# FREZZbigV02.net
KiCad netlist of a schematic drawn in EAGLE
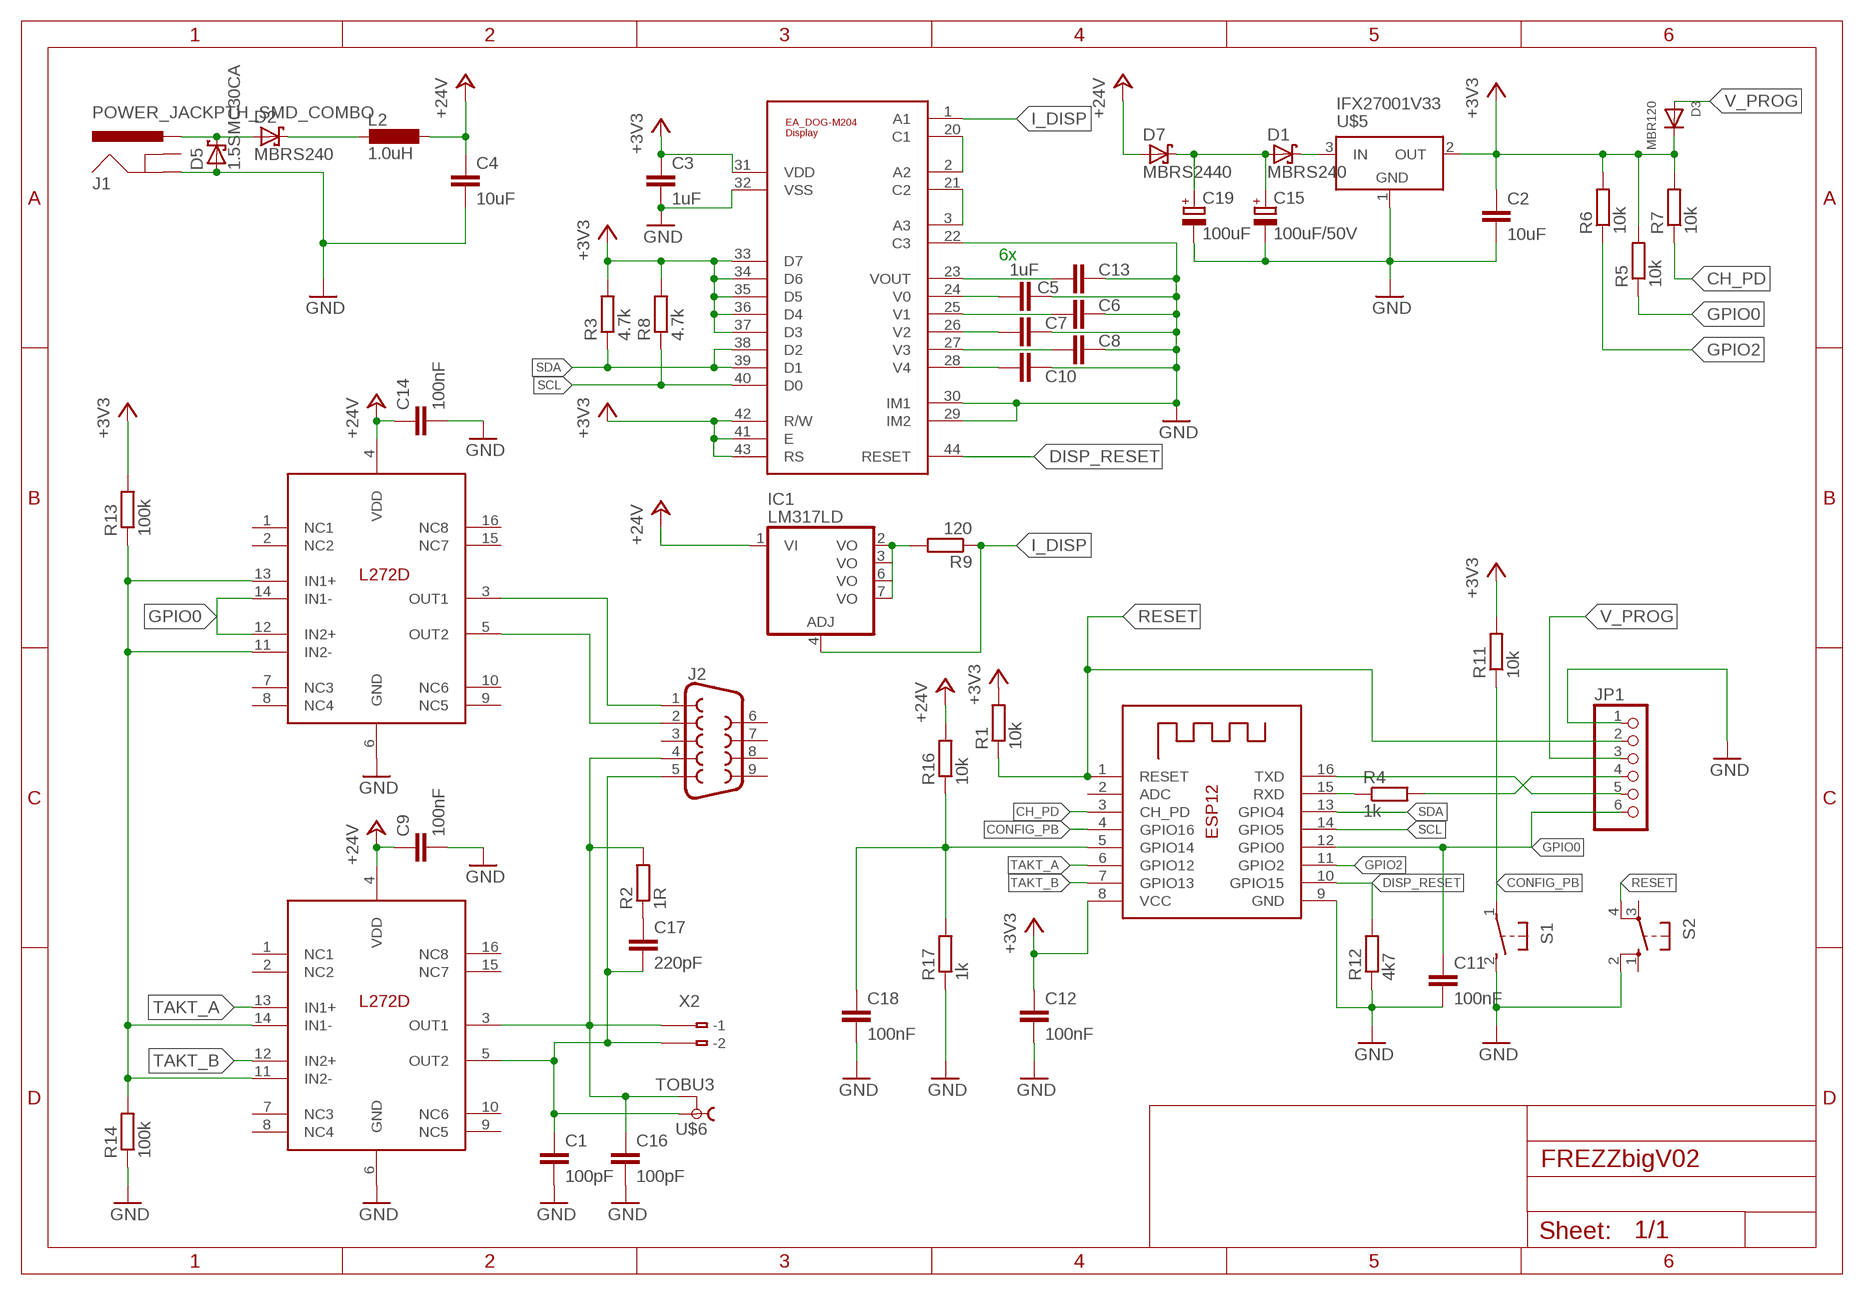
[diagram p0: schematic, sheet 1]

(export (version "E")
  (design (tool "Eeschema 10.0.6"))
  (components
    (comp (ref "C1")
      (value "100pF")
      (footprint "eagle-import:C0603K")
      (libsource (lib "eagle-import") (part "C-EUC0603K"))
    )
    (comp (ref "C2")
      (value "10uF")
      (footprint "eagle-import:C0603K")
      (libsource (lib "eagle-import") (part "C-EUC0603K"))
    )
    (comp (ref "C3")
      (value "1uF")
      (footprint "eagle-import:C0603K")
      (libsource (lib "eagle-import") (part "C-EUC0603K"))
    )
    (comp (ref "C4")
      (value "10uF")
      (footprint "eagle-import:C1210K")
      (libsource (lib "eagle-import") (part "C-EUC1210K"))
    )
    (comp (ref "C5")
      (value "1uF")
      (footprint "eagle-import:C0603K")
      (libsource (lib "eagle-import") (part "C-EUC0603K"))
    )
    (comp (ref "C6")
      (value "1uF")
      (footprint "eagle-import:C0603K")
      (libsource (lib "eagle-import") (part "C-EUC0603K"))
    )
    (comp (ref "C7")
      (value "1uF")
      (footprint "eagle-import:C0603K")
      (libsource (lib "eagle-import") (part "C-EUC0603K"))
    )
    (comp (ref "C8")
      (value "1uF")
      (footprint "eagle-import:C0603K")
      (libsource (lib "eagle-import") (part "C-EUC0603K"))
    )
    (comp (ref "C9")
      (value "100nF")
      (footprint "eagle-import:C0603K")
      (libsource (lib "eagle-import") (part "C-EUC0603K"))
    )
    (comp (ref "C10")
      (value "1uF")
      (footprint "eagle-import:C0603K")
      (libsource (lib "eagle-import") (part "C-EUC0603K"))
    )
    (comp (ref "C11")
      (value "100nF")
      (footprint "eagle-import:C0603K")
      (libsource (lib "eagle-import") (part "C-EUC0603K"))
    )
    (comp (ref "C12")
      (value "100nF")
      (footprint "eagle-import:C0603K")
      (libsource (lib "eagle-import") (part "C-EUC0603K"))
    )
    (comp (ref "C13")
      (value "1uF")
      (footprint "eagle-import:C0603K")
      (libsource (lib "eagle-import") (part "C-EUC0603K"))
    )
    (comp (ref "C14")
      (value "100nF")
      (footprint "eagle-import:C0603K")
      (libsource (lib "eagle-import") (part "C-EUC0603K"))
    )
    (comp (ref "C15")
      (value "100uF/50V")
      (footprint "eagle-import:PANASONIC_F")
      (libsource (lib "eagle-import") (part "CPOL-EUF"))
    )
    (comp (ref "C16")
      (value "100pF")
      (footprint "eagle-import:C0603K")
      (libsource (lib "eagle-import") (part "C-EUC0603K"))
    )
    (comp (ref "C17")
      (value "220pF")
      (footprint "eagle-import:C0603K")
      (libsource (lib "eagle-import") (part "C-EUC0603K"))
    )
    (comp (ref "C18")
      (value "100nF")
      (footprint "eagle-import:C0603K")
      (libsource (lib "eagle-import") (part "C-EUC0603K"))
    )
    (comp (ref "C19")
      (value "100uF")
      (footprint "eagle-import:E7,5-18")
      (libsource (lib "eagle-import") (part "CPOL-EUE7.5-18"))
    )
    (comp (ref "D1")
      (value "MBRS240")
      (footprint "eagle-import:SMB")
      (libsource (lib "eagle-import") (part "SCHOTTKY-DIODESMD"))
    )
    (comp (ref "D2")
      (value "MBRS240")
      (footprint "eagle-import:SMB")
      (libsource (lib "eagle-import") (part "SCHOTTKY-DIODESMD"))
    )
    (comp (ref "D3")
      (value "MBR120")
      (footprint "eagle-import:SOD-123")
      (libsource (lib "eagle-import") (part "DIODESOD-123"))
    )
    (comp (ref "D5")
      (value "1.5SMC30CA")
      (footprint "eagle-import:SMC")
      (libsource (lib "eagle-import") (part "SCHOTTKY-DIODESMC"))
    )
    (comp (ref "D7")
      (value "MBRS2440")
      (footprint "eagle-import:SMB")
      (libsource (lib "eagle-import") (part "SCHOTTKY-DIODESMD"))
    )
    (comp (ref "IC1")
      (value "LM317LD")
      (footprint "eagle-import:SO08")
      (libsource (lib "eagle-import") (part "LM317LD"))
    )
    (comp (ref "J1")
      (value "POWER_JACKPTH_SMD_COMBO")
      (footprint "eagle-import:POWER_JACK_COMBO")
      (libsource (lib "eagle-import") (part "POWER_JACKPTH_SMD_COMBO"))
    )
    (comp (ref "J2")
      (value "DB9FEMALE")
      (footprint "eagle-import:DB9")
      (libsource (lib "eagle-import") (part "DB9FEMALE"))
    )
    (comp (ref "JP1")
      (value "PINHD-1X6")
      (footprint "eagle-import:1X06")
      (libsource (lib "eagle-import") (part "PINHD-1X6"))
    )
    (comp (ref "L2")
      (value "1.0uH")
      (footprint "eagle-import:L3230M")
      (libsource (lib "eagle-import") (part "L-EUL3230M"))
    )
    (comp (ref "R1")
      (value "10k")
      (footprint "eagle-import:M1206")
      (libsource (lib "eagle-import") (part "R-EU_M1206"))
    )
    (comp (ref "R2")
      (value "1R")
      (footprint "eagle-import:M1206")
      (libsource (lib "eagle-import") (part "R-EU_M1206"))
    )
    (comp (ref "R3")
      (value "4.7k")
      (footprint "eagle-import:M1206")
      (libsource (lib "eagle-import") (part "R-EU_M1206"))
    )
    (comp (ref "R4")
      (value "1k")
      (footprint "eagle-import:M1206")
      (libsource (lib "eagle-import") (part "R-EU_M1206"))
    )
    (comp (ref "R5")
      (value "10k")
      (footprint "eagle-import:M1206")
      (libsource (lib "eagle-import") (part "R-EU_M1206"))
    )
    (comp (ref "R6")
      (value "10k")
      (footprint "eagle-import:M1206")
      (libsource (lib "eagle-import") (part "R-EU_M1206"))
    )
    (comp (ref "R7")
      (value "10k")
      (footprint "eagle-import:M1206")
      (libsource (lib "eagle-import") (part "R-EU_M1206"))
    )
    (comp (ref "R8")
      (value "4.7k")
      (footprint "eagle-import:M1206")
      (libsource (lib "eagle-import") (part "R-EU_M1206"))
    )
    (comp (ref "R9")
      (value "120")
      (footprint "eagle-import:M1206")
      (libsource (lib "eagle-import") (part "R-EU_M1206"))
    )
    (comp (ref "R11")
      (value "10k")
      (footprint "eagle-import:M1206")
      (libsource (lib "eagle-import") (part "R-EU_M1206"))
    )
    (comp (ref "R12")
      (value "4k7")
      (footprint "eagle-import:M1206")
      (libsource (lib "eagle-import") (part "R-EU_M1206"))
    )
    (comp (ref "R13")
      (value "100k")
      (footprint "eagle-import:M1206")
      (libsource (lib "eagle-import") (part "R-EU_M1206"))
    )
    (comp (ref "R14")
      (value "100k")
      (footprint "eagle-import:M1206")
      (libsource (lib "eagle-import") (part "R-EU_M1206"))
    )
    (comp (ref "R16")
      (value "10k")
      (footprint "eagle-import:M1206")
      (libsource (lib "eagle-import") (part "R-EU_M1206"))
    )
    (comp (ref "R17")
      (value "1k")
      (footprint "eagle-import:M1206")
      (libsource (lib "eagle-import") (part "R-EU_M1206"))
    )
    (comp (ref "S1")
      (value "31-XX")
      (footprint "eagle-import:B3F-31XX")
      (fields (field (name "MPN") "B3F-3100"))
      (libsource (lib "eagle-import") (part "31-XX"))
    )
    (comp (ref "S2")
      (value "10-XX")
      (footprint "eagle-import:B3F-10XX")
      (fields (field (name "MPN") "B3F-1000"))
      (libsource (lib "eagle-import") (part "10-XX"))
    )
    (comp (ref "U$1")
      (value "EA_DOG-M204-DISPLAY")
      (footprint "eagle-import:E_DOG-M204_DISPLAY")
      (libsource (lib "eagle-import") (part "EA_DOG-M204-DISPLAY"))
    )
    (comp (ref "U$2")
      (value "L272D")
      (footprint "eagle-import:SO16")
      (libsource (lib "eagle-import") (part "L272D"))
    )
    (comp (ref "U$3")
      (value "L272D")
      (footprint "eagle-import:SO16")
      (libsource (lib "eagle-import") (part "L272D"))
    )
    (comp (ref "U$5")
      (value "IFX27001V33")
      (footprint "eagle-import:TO252")
      (libsource (lib "eagle-import") (part "IFX27001"))
    )
    (comp (ref "U$6")
      (value "TOBU3")
      (footprint "eagle-import:TOBU3-REICHELT")
      (libsource (lib "eagle-import") (part "TOBU3-REICHELT"))
    )
    (comp (ref "X1")
      (value "ESP-12")
      (footprint "eagle-import:ESP-12")
      (libsource (lib "eagle-import") (part "ESP-12"))
    )
    (comp (ref "X2")
      (value "233-102")
      (footprint "eagle-import:233-102")
      (libsource (lib "eagle-import") (part "233-102"))
    )
  )
  (nets
    (net (code "1") (name "+3V3") (class "Default")
      (node (ref "C12") (pin "1") (pinfunction "1_1") (pintype "passive"))
      (node (ref "C2") (pin "1") (pinfunction "1_1") (pintype "passive"))
      (node (ref "C3") (pin "1") (pinfunction "1_1") (pintype "passive"))
      (node (ref "D3") (pin "C") (pinfunction "C_C") (pintype "passive"))
      (node (ref "R1") (pin "2") (pinfunction "2_2") (pintype "passive"))
      (node (ref "R11") (pin "2") (pinfunction "2_2") (pintype "passive"))
      (node (ref "R13") (pin "2") (pinfunction "2_2") (pintype "passive"))
      (node (ref "R3") (pin "2") (pinfunction "2_2") (pintype "passive"))
      (node (ref "R5") (pin "2") (pinfunction "2_2") (pintype "passive"))
      (node (ref "R6") (pin "2") (pinfunction "2_2") (pintype "passive"))
      (node (ref "R7") (pin "2") (pinfunction "2_2") (pintype "passive"))
      (node (ref "R8") (pin "2") (pinfunction "2_2") (pintype "passive"))
      (node (ref "U$1") (pin "31") (pinfunction "VDD_31") (pintype "power_in"))
      (node (ref "U$1") (pin "33") (pinfunction "D7_33") (pintype "bidirectional"))
      (node (ref "U$1") (pin "34") (pinfunction "D6_34") (pintype "bidirectional"))
      (node (ref "U$1") (pin "35") (pinfunction "D5_35") (pintype "bidirectional"))
      (node (ref "U$1") (pin "36") (pinfunction "D4_36") (pintype "bidirectional"))
      (node (ref "U$1") (pin "37") (pinfunction "D3_37") (pintype "bidirectional"))
      (node (ref "U$1") (pin "41") (pinfunction "E_41") (pintype "bidirectional"))
      (node (ref "U$1") (pin "42") (pinfunction "R/W_42") (pintype "bidirectional"))
      (node (ref "U$1") (pin "43") (pinfunction "RS_43") (pintype "bidirectional"))
      (node (ref "U$5") (pin "2") (pinfunction "OUT_2") (pintype "output"))
      (node (ref "X1") (pin "8") (pinfunction "VCC_8") (pintype "power_in"))
    )
    (net (code "2") (name "+24V") (class "Default")
      (node (ref "C14") (pin "1") (pinfunction "1_1") (pintype "passive"))
      (node (ref "C4") (pin "1") (pinfunction "1_1") (pintype "passive"))
      (node (ref "C9") (pin "1") (pinfunction "1_1") (pintype "passive"))
      (node (ref "D7") (pin "A") (pinfunction "A_A") (pintype "passive"))
      (node (ref "IC1") (pin "1") (pinfunction "VI_1") (pintype "input"))
      (node (ref "L2") (pin "1") (pinfunction "1_1") (pintype "passive"))
      (node (ref "R16") (pin "2") (pinfunction "2_2") (pintype "passive"))
      (node (ref "U$2") (pin "4") (pinfunction "VDD_4") (pintype "power_in"))
      (node (ref "U$3") (pin "4") (pinfunction "VDD_4") (pintype "power_in"))
    )
    (net (code "3") (name "CH_PD") (class "Default")
      (node (ref "R7") (pin "1") (pinfunction "1_1") (pintype "passive"))
      (node (ref "X1") (pin "3") (pinfunction "CH_PD_3") (pintype "input"))
    )
    (net (code "4") (name "CONFIG_PB") (class "Default")
      (node (ref "R11") (pin "1") (pinfunction "1_1") (pintype "passive"))
      (node (ref "S1") (pin "1") (pinfunction "P_1") (pintype "passive"))
      (node (ref "X1") (pin "4") (pinfunction "GPIO16_4") (pintype "bidirectional"))
    )
    (net (code "5") (name "DISP_RESET") (class "Default")
      (node (ref "R12") (pin "2") (pinfunction "2_2") (pintype "passive"))
      (node (ref "U$1") (pin "44") (pinfunction "RESET_44") (pintype "bidirectional"))
      (node (ref "X1") (pin "10") (pinfunction "GPIO15_10") (pintype "bidirectional"))
    )
    (net (code "6") (name "GND") (class "Default")
      (node (ref "C1") (pin "2") (pinfunction "2_2") (pintype "passive"))
      (node (ref "C10") (pin "1") (pinfunction "1_1") (pintype "passive"))
      (node (ref "C11") (pin "2") (pinfunction "2_2") (pintype "passive"))
      (node (ref "C12") (pin "2") (pinfunction "2_2") (pintype "passive"))
      (node (ref "C13") (pin "1") (pinfunction "1_1") (pintype "passive"))
      (node (ref "C14") (pin "2") (pinfunction "2_2") (pintype "passive"))
      (node (ref "C15") (pin "-") (pinfunction "-_-") (pintype "passive"))
      (node (ref "C16") (pin "2") (pinfunction "2_2") (pintype "passive"))
      (node (ref "C18") (pin "2") (pinfunction "2_2") (pintype "passive"))
      (node (ref "C19") (pin "-") (pinfunction "-_-") (pintype "passive"))
      (node (ref "C2") (pin "2") (pinfunction "2_2") (pintype "passive"))
      (node (ref "C3") (pin "2") (pinfunction "2_2") (pintype "passive"))
      (node (ref "C4") (pin "2") (pinfunction "2_2") (pintype "passive"))
      (node (ref "C5") (pin "1") (pinfunction "1_1") (pintype "passive"))
      (node (ref "C6") (pin "1") (pinfunction "1_1") (pintype "passive"))
      (node (ref "C7") (pin "1") (pinfunction "1_1") (pintype "passive"))
      (node (ref "C8") (pin "1") (pinfunction "1_1") (pintype "passive"))
      (node (ref "C9") (pin "2") (pinfunction "2_2") (pintype "passive"))
      (node (ref "D5") (pin "A") (pinfunction "A_A") (pintype "passive"))
      (node (ref "J1") (pin "GND@1") (pinfunction "GND_GND@1") (pintype "bidirectional"))
      (node (ref "JP1") (pin "1") (pinfunction "1_1") (pintype "passive"))
      (node (ref "R12") (pin "1") (pinfunction "1_1") (pintype "passive"))
      (node (ref "R14") (pin "1") (pinfunction "1_1") (pintype "passive"))
      (node (ref "R17") (pin "1") (pinfunction "1_1") (pintype "passive"))
      (node (ref "S1") (pin "2") (pinfunction "S_2") (pintype "passive"))
      (node (ref "S2") (pin "2") (pinfunction "S1_2") (pintype "passive"))
      (node (ref "U$1") (pin "22") (pinfunction "C3_22") (pintype "bidirectional"))
      (node (ref "U$1") (pin "29") (pinfunction "IM2_29") (pintype "bidirectional"))
      (node (ref "U$1") (pin "30") (pinfunction "IM1_30") (pintype "bidirectional"))
      (node (ref "U$1") (pin "32") (pinfunction "VSS_32") (pintype "power_in"))
      (node (ref "U$2") (pin "6") (pinfunction "GND_6") (pintype "power_in"))
      (node (ref "U$3") (pin "6") (pinfunction "GND_6") (pintype "power_in"))
      (node (ref "U$5") (pin "1") (pinfunction "GND_1") (pintype "power_in"))
      (node (ref "X1") (pin "9") (pinfunction "GND_9") (pintype "power_in"))
    )
    (net (code "7") (name "GPIO0") (class "Default")
      (node (ref "C11") (pin "1") (pinfunction "1_1") (pintype "passive"))
      (node (ref "JP1") (pin "6") (pinfunction "6_6") (pintype "passive"))
      (node (ref "R5") (pin "1") (pinfunction "1_1") (pintype "passive"))
      (node (ref "U$3") (pin "12") (pinfunction "IN2+_12") (pintype "bidirectional"))
      (node (ref "U$3") (pin "14") (pinfunction "IN1-_14") (pintype "bidirectional"))
      (node (ref "X1") (pin "12") (pinfunction "GPIO0_12") (pintype "bidirectional"))
    )
    (net (code "8") (name "GPIO2") (class "Default")
      (node (ref "R6") (pin "1") (pinfunction "1_1") (pintype "passive"))
      (node (ref "X1") (pin "11") (pinfunction "GPIO2_11") (pintype "bidirectional"))
    )
    (net (code "9") (name "I_DISP") (class "Default")
      (node (ref "IC1") (pin "4") (pinfunction "ADJ_4") (pintype "input"))
      (node (ref "R9") (pin "1") (pinfunction "1_1") (pintype "passive"))
      (node (ref "U$1") (pin "1") (pinfunction "A1_1") (pintype "bidirectional"))
    )
    (net (code "10") (name "Net-(C15-Pad+)") (class "Default")
      (node (ref "C15") (pin "+") (pinfunction "+_+") (pintype "passive"))
      (node (ref "C19") (pin "+") (pinfunction "+_+") (pintype "passive"))
      (node (ref "D1") (pin "A") (pinfunction "A_A") (pintype "passive"))
      (node (ref "D7") (pin "C") (pinfunction "C_C") (pintype "passive"))
    )
    (net (code "11") (name "Net-(C17-Pad1)") (class "Default")
      (node (ref "C17") (pin "1") (pinfunction "1_1") (pintype "passive"))
      (node (ref "R2") (pin "1") (pinfunction "1_1") (pintype "passive"))
    )
    (net (code "12") (name "Net-(D2-PadC)") (class "Default")
      (node (ref "D2") (pin "C") (pinfunction "C_C") (pintype "passive"))
      (node (ref "L2") (pin "2") (pinfunction "2_2") (pintype "passive"))
    )
    (net (code "13") (name "Net-(IC1-VO-Pad2)") (class "Default")
      (node (ref "IC1") (pin "2") (pinfunction "VO_2") (pintype "passive"))
      (node (ref "IC1") (pin "3") (pinfunction "VO_3") (pintype "passive"))
      (node (ref "IC1") (pin "6") (pinfunction "VO_6") (pintype "passive"))
      (node (ref "IC1") (pin "7") (pinfunction "VO_7") (pintype "passive"))
      (node (ref "R9") (pin "2") (pinfunction "2_2") (pintype "passive"))
    )
    (net (code "14") (name "Net-(J1-PWR)") (class "Default")
      (node (ref "D2") (pin "A") (pinfunction "A_A") (pintype "passive"))
      (node (ref "D5") (pin "C") (pinfunction "C_C") (pintype "passive"))
      (node (ref "J1") (pin "POWER") (pinfunction "PWR_POWER") (pintype "bidirectional"))
    )
    (net (code "15") (name "Net-(JP1-Pad4)") (class "Default")
      (node (ref "JP1") (pin "4") (pinfunction "4_4") (pintype "passive"))
      (node (ref "R4") (pin "2") (pinfunction "2_2") (pintype "passive"))
    )
    (net (code "16") (name "Net-(U$1-A2)") (class "Default")
      (node (ref "U$1") (pin "2") (pinfunction "A2_2") (pintype "bidirectional"))
      (node (ref "U$1") (pin "20") (pinfunction "C1_20") (pintype "bidirectional"))
    )
    (net (code "17") (name "Net-(U$1-A3)") (class "Default")
      (node (ref "U$1") (pin "21") (pinfunction "C2_21") (pintype "bidirectional"))
      (node (ref "U$1") (pin "3") (pinfunction "A3_3") (pintype "bidirectional"))
    )
    (net (code "18") (name "Net-(U$1-V0)") (class "Default")
      (node (ref "C5") (pin "2") (pinfunction "2_2") (pintype "passive"))
      (node (ref "U$1") (pin "24") (pinfunction "V0_24") (pintype "bidirectional"))
    )
    (net (code "19") (name "Net-(U$1-V1)") (class "Default")
      (node (ref "C6") (pin "2") (pinfunction "2_2") (pintype "passive"))
      (node (ref "U$1") (pin "25") (pinfunction "V1_25") (pintype "bidirectional"))
    )
    (net (code "20") (name "Net-(U$1-V2)") (class "Default")
      (node (ref "C7") (pin "2") (pinfunction "2_2") (pintype "passive"))
      (node (ref "U$1") (pin "26") (pinfunction "V2_26") (pintype "bidirectional"))
    )
    (net (code "21") (name "Net-(U$1-V3)") (class "Default")
      (node (ref "C8") (pin "2") (pinfunction "2_2") (pintype "passive"))
      (node (ref "U$1") (pin "27") (pinfunction "V3_27") (pintype "bidirectional"))
    )
    (net (code "22") (name "Net-(U$1-V4)") (class "Default")
      (node (ref "C10") (pin "2") (pinfunction "2_2") (pintype "passive"))
      (node (ref "U$1") (pin "28") (pinfunction "V4_28") (pintype "bidirectional"))
    )
    (net (code "23") (name "Net-(U$1-VOUT)") (class "Default")
      (node (ref "C13") (pin "2") (pinfunction "2_2") (pintype "passive"))
      (node (ref "U$1") (pin "23") (pinfunction "VOUT_23") (pintype "bidirectional"))
    )
    (net (code "24") (name "Net-(U$2-IN1-)") (class "Default")
      (node (ref "R13") (pin "1") (pinfunction "1_1") (pintype "passive"))
      (node (ref "R14") (pin "2") (pinfunction "2_2") (pintype "passive"))
      (node (ref "U$2") (pin "11") (pinfunction "IN2-_11") (pintype "bidirectional"))
      (node (ref "U$2") (pin "14") (pinfunction "IN1-_14") (pintype "bidirectional"))
      (node (ref "U$3") (pin "11") (pinfunction "IN2-_11") (pintype "bidirectional"))
      (node (ref "U$3") (pin "13") (pinfunction "IN1+_13") (pintype "input"))
    )
    (net (code "25") (name "Net-(U$2-OUT1)") (class "Default")
      (node (ref "C16") (pin "1") (pinfunction "1_1") (pintype "passive"))
      (node (ref "J2") (pin "4") (pinfunction "4_4") (pintype "passive"))
      (node (ref "R2") (pin "2") (pinfunction "2_2") (pintype "passive"))
      (node (ref "U$2") (pin "3") (pinfunction "OUT1_3") (pintype "output"))
      (node (ref "U$6") (pin "2") (pinfunction "2_2") (pintype "passive"))
      (node (ref "U$6") (pin "2@1") (pinfunction "2_2@1") (pintype "passive"))
      (node (ref "U$6") (pin "2@2") (pinfunction "2_2@2") (pintype "passive"))
      (node (ref "X2") (pin "B1") (pinfunction "B-1_B1") (pintype "passive"))
    )
    (net (code "26") (name "Net-(U$2-OUT2)") (class "Default")
      (node (ref "C1") (pin "1") (pinfunction "1_1") (pintype "passive"))
      (node (ref "C17") (pin "2") (pinfunction "2_2") (pintype "passive"))
      (node (ref "J2") (pin "5") (pinfunction "5_5") (pintype "passive"))
      (node (ref "U$2") (pin "5") (pinfunction "OUT2_5") (pintype "output"))
      (node (ref "U$6") (pin "1") (pinfunction "1_1") (pintype "passive"))
      (node (ref "X2") (pin "B2") (pinfunction "B-2_B2") (pintype "passive"))
    )
    (net (code "27") (name "Net-(U$3-OUT1)") (class "Default")
      (node (ref "J2") (pin "1") (pinfunction "1_1") (pintype "passive"))
      (node (ref "U$3") (pin "3") (pinfunction "OUT1_3") (pintype "output"))
    )
    (net (code "28") (name "Net-(U$3-OUT2)") (class "Default")
      (node (ref "J2") (pin "2") (pinfunction "2_2") (pintype "passive"))
      (node (ref "U$3") (pin "5") (pinfunction "OUT2_5") (pintype "output"))
    )
    (net (code "29") (name "Net-(U$5-IN)") (class "Default")
      (node (ref "D1") (pin "C") (pinfunction "C_C") (pintype "passive"))
      (node (ref "U$5") (pin "3") (pinfunction "IN_3") (pintype "input"))
    )
    (net (code "30") (name "Net-(X1-GPIO14)") (class "Default")
      (node (ref "C18") (pin "1") (pinfunction "1_1") (pintype "passive"))
      (node (ref "R16") (pin "1") (pinfunction "1_1") (pintype "passive"))
      (node (ref "R17") (pin "2") (pinfunction "2_2") (pintype "passive"))
      (node (ref "X1") (pin "5") (pinfunction "GPIO14_5") (pintype "bidirectional"))
    )
    (net (code "31") (name "Net-(X1-RXD)") (class "Default")
      (node (ref "R4") (pin "1") (pinfunction "1_1") (pintype "passive"))
      (node (ref "X1") (pin "15") (pinfunction "RXD_15") (pintype "input"))
    )
    (net (code "32") (name "Net-(X1-TXD)") (class "Default")
      (node (ref "JP1") (pin "5") (pinfunction "5_5") (pintype "passive"))
      (node (ref "X1") (pin "16") (pinfunction "TXD_16") (pintype "output"))
    )
    (net (code "33") (name "RESET") (class "Default")
      (node (ref "JP1") (pin "2") (pinfunction "2_2") (pintype "passive"))
      (node (ref "R1") (pin "1") (pinfunction "1_1") (pintype "passive"))
      (node (ref "S2") (pin "4") (pinfunction "P1_4") (pintype "passive"))
      (node (ref "X1") (pin "1") (pinfunction "RESET_1") (pintype "input"))
    )
    (net (code "34") (name "SCL") (class "Default")
      (node (ref "R8") (pin "1") (pinfunction "1_1") (pintype "passive"))
      (node (ref "U$1") (pin "40") (pinfunction "D0_40") (pintype "bidirectional"))
      (node (ref "X1") (pin "14") (pinfunction "GPIO5_14") (pintype "bidirectional"))
    )
    (net (code "35") (name "SDA") (class "Default")
      (node (ref "R3") (pin "1") (pinfunction "1_1") (pintype "passive"))
      (node (ref "U$1") (pin "38") (pinfunction "D2_38") (pintype "bidirectional"))
      (node (ref "U$1") (pin "39") (pinfunction "D1_39") (pintype "bidirectional"))
      (node (ref "X1") (pin "13") (pinfunction "GPIO4_13") (pintype "bidirectional"))
    )
    (net (code "36") (name "TAKT_A") (class "Default")
      (node (ref "U$2") (pin "13") (pinfunction "IN1+_13") (pintype "input"))
      (node (ref "X1") (pin "6") (pinfunction "GPIO12_6") (pintype "bidirectional"))
    )
    (net (code "37") (name "TAKT_B") (class "Default")
      (node (ref "U$2") (pin "12") (pinfunction "IN2+_12") (pintype "bidirectional"))
      (node (ref "X1") (pin "7") (pinfunction "GPIO13_7") (pintype "bidirectional"))
    )
    (net (code "38") (name "V_PROG") (class "Default")
      (node (ref "D3") (pin "A") (pinfunction "A_A") (pintype "passive"))
      (node (ref "JP1") (pin "3") (pinfunction "3_3") (pintype "passive"))
    )
    (net (code "39") (name "unconnected-(J1-GNDBREAK-PadGND)") (class "Default")
      (node (ref "J1") (pin "GND") (pinfunction "GNDBREAK_GND") (pintype "bidirectional"))
    )
    (net (code "40") (name "unconnected-(J2-Pad3)") (class "Default")
      (node (ref "J2") (pin "3") (pinfunction "3_3") (pintype "passive"))
    )
    (net (code "41") (name "unconnected-(J2-Pad6)") (class "Default")
      (node (ref "J2") (pin "6") (pinfunction "6_6") (pintype "passive"))
    )
    (net (code "42") (name "unconnected-(J2-Pad7)") (class "Default")
      (node (ref "J2") (pin "7") (pinfunction "7_7") (pintype "passive"))
    )
    (net (code "43") (name "unconnected-(J2-Pad8)") (class "Default")
      (node (ref "J2") (pin "8") (pinfunction "8_8") (pintype "passive"))
    )
    (net (code "44") (name "unconnected-(J2-Pad9)") (class "Default")
      (node (ref "J2") (pin "9") (pinfunction "9_9") (pintype "passive"))
    )
    (net (code "45") (name "unconnected-(S2-P-Pad3)") (class "Default")
      (node (ref "S2") (pin "3") (pinfunction "P_3") (pintype "passive"))
    )
    (net (code "46") (name "unconnected-(S2-S-Pad1)") (class "Default")
      (node (ref "S2") (pin "1") (pinfunction "S_1") (pintype "passive"))
    )
    (net (code "47") (name "unconnected-(U$2-NC1-Pad1)") (class "Default")
      (node (ref "U$2") (pin "1") (pinfunction "NC1_1") (pintype "no_connect"))
    )
    (net (code "48") (name "unconnected-(U$2-NC2-Pad2)") (class "Default")
      (node (ref "U$2") (pin "2") (pinfunction "NC2_2") (pintype "bidirectional"))
    )
    (net (code "49") (name "unconnected-(U$2-NC3-Pad7)") (class "Default")
      (node (ref "U$2") (pin "7") (pinfunction "NC3_7") (pintype "bidirectional"))
    )
    (net (code "50") (name "unconnected-(U$2-NC4-Pad8)") (class "Default")
      (node (ref "U$2") (pin "8") (pinfunction "NC4_8") (pintype "bidirectional"))
    )
    (net (code "51") (name "unconnected-(U$2-NC5-Pad9)") (class "Default")
      (node (ref "U$2") (pin "9") (pinfunction "NC5_9") (pintype "bidirectional"))
    )
    (net (code "52") (name "unconnected-(U$2-NC6-Pad10)") (class "Default")
      (node (ref "U$2") (pin "10") (pinfunction "NC6_10") (pintype "bidirectional"))
    )
    (net (code "53") (name "unconnected-(U$2-NC7-Pad15)") (class "Default")
      (node (ref "U$2") (pin "15") (pinfunction "NC7_15") (pintype "bidirectional"))
    )
    (net (code "54") (name "unconnected-(U$2-NC8-Pad16)") (class "Default")
      (node (ref "U$2") (pin "16") (pinfunction "NC8_16") (pintype "bidirectional"))
    )
    (net (code "55") (name "unconnected-(U$3-NC1-Pad1)") (class "Default")
      (node (ref "U$3") (pin "1") (pinfunction "NC1_1") (pintype "no_connect"))
    )
    (net (code "56") (name "unconnected-(U$3-NC2-Pad2)") (class "Default")
      (node (ref "U$3") (pin "2") (pinfunction "NC2_2") (pintype "bidirectional"))
    )
    (net (code "57") (name "unconnected-(U$3-NC3-Pad7)") (class "Default")
      (node (ref "U$3") (pin "7") (pinfunction "NC3_7") (pintype "bidirectional"))
    )
    (net (code "58") (name "unconnected-(U$3-NC4-Pad8)") (class "Default")
      (node (ref "U$3") (pin "8") (pinfunction "NC4_8") (pintype "bidirectional"))
    )
    (net (code "59") (name "unconnected-(U$3-NC5-Pad9)") (class "Default")
      (node (ref "U$3") (pin "9") (pinfunction "NC5_9") (pintype "bidirectional"))
    )
    (net (code "60") (name "unconnected-(U$3-NC6-Pad10)") (class "Default")
      (node (ref "U$3") (pin "10") (pinfunction "NC6_10") (pintype "bidirectional"))
    )
    (net (code "61") (name "unconnected-(U$3-NC7-Pad15)") (class "Default")
      (node (ref "U$3") (pin "15") (pinfunction "NC7_15") (pintype "bidirectional"))
    )
    (net (code "62") (name "unconnected-(U$3-NC8-Pad16)") (class "Default")
      (node (ref "U$3") (pin "16") (pinfunction "NC8_16") (pintype "bidirectional"))
    )
    (net (code "63") (name "unconnected-(X1-ADC-Pad2)") (class "Default")
      (node (ref "X1") (pin "2") (pinfunction "ADC_2") (pintype "passive"))
    )
    (net (code "64") (name "unconnected-(X2--1-PadA1)") (class "Default")
      (node (ref "X2") (pin "A1") (pinfunction "-1_A1") (pintype "passive"))
    )
    (net (code "65") (name "unconnected-(X2--2-PadA2)") (class "Default")
      (node (ref "X2") (pin "A2") (pinfunction "-2_A2") (pintype "passive"))
    )
  )
)
